# PowerMeasuringIC.net
KiCad netlist of a schematic drawn in EAGLE
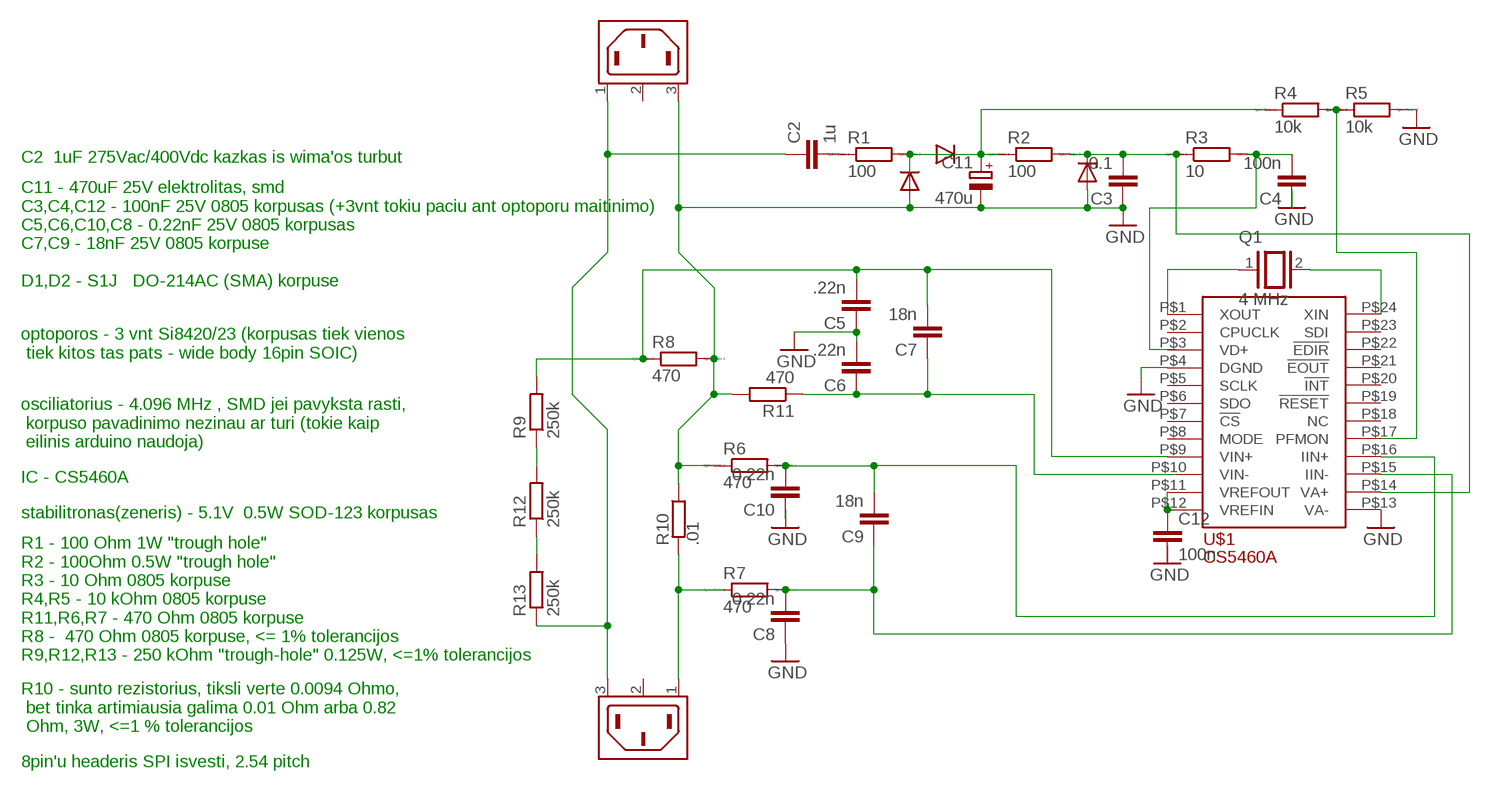
[diagram p0: schematic, sheet 1]

(export (version "E")
  (design (tool "Eeschema 10.0.6"))
  (components
    (comp (ref "C2")
      (value "1u")
      (footprint "eagle-import:C1206")
      (libsource (lib "eagle-import") (part "C-EUC1206"))
    )
    (comp (ref "C3")
      (value "0.1")
      (footprint "eagle-import:C1206")
      (libsource (lib "eagle-import") (part "C-EUC1206"))
    )
    (comp (ref "C4")
      (value "100n")
      (footprint "eagle-import:C1206")
      (libsource (lib "eagle-import") (part "C-EUC1206"))
    )
    (comp (ref "C5")
      (value ".22n")
      (footprint "eagle-import:C1206")
      (libsource (lib "eagle-import") (part "C-EUC1206"))
    )
    (comp (ref "C6")
      (value ".22n")
      (footprint "eagle-import:C1206")
      (libsource (lib "eagle-import") (part "C-EUC1206"))
    )
    (comp (ref "C7")
      (value "18n")
      (footprint "eagle-import:C1206")
      (libsource (lib "eagle-import") (part "C-EUC1206"))
    )
    (comp (ref "C8")
      (value "0.22n")
      (footprint "eagle-import:C1206")
      (libsource (lib "eagle-import") (part "C-EUC1206"))
    )
    (comp (ref "C9")
      (value "18n")
      (footprint "eagle-import:C1206")
      (libsource (lib "eagle-import") (part "C-EUC1206"))
    )
    (comp (ref "C10")
      (value "0.22n")
      (footprint "eagle-import:C1206")
      (libsource (lib "eagle-import") (part "C-EUC1206"))
    )
    (comp (ref "C11")
      (value "470u")
      (footprint "eagle-import:153CLV-0807")
      (libsource (lib "eagle-import") (part "CPOL-EU153CLV-0807"))
    )
    (comp (ref "C12")
      (value "100n")
      (footprint "eagle-import:C025-024X044")
      (libsource (lib "eagle-import") (part "C-EU025-024X044"))
    )
    (comp (ref "Q1")
      (value "4 MHz")
      (footprint "eagle-import:Q")
      (libsource (lib "eagle-import") (part "XTAL"))
    )
    (comp (ref "R1")
      (value "100")
      (footprint "eagle-import:R4527")
      (libsource (lib "eagle-import") (part "RR4527"))
    )
    (comp (ref "R2")
      (value "100")
      (footprint "eagle-import:R4527")
      (libsource (lib "eagle-import") (part "RR4527"))
    )
    (comp (ref "R3")
      (value "10")
      (footprint "eagle-import:R4527")
      (libsource (lib "eagle-import") (part "RR4527"))
    )
    (comp (ref "R4")
      (value "10k")
      (footprint "eagle-import:R4527")
      (libsource (lib "eagle-import") (part "RR4527"))
    )
    (comp (ref "R5")
      (value "10k")
      (footprint "eagle-import:R4527")
      (libsource (lib "eagle-import") (part "RR4527"))
    )
    (comp (ref "R6")
      (value "470")
      (footprint "eagle-import:R4527")
      (libsource (lib "eagle-import") (part "RR4527"))
    )
    (comp (ref "R7")
      (value "470")
      (footprint "eagle-import:R4527")
      (libsource (lib "eagle-import") (part "RR4527"))
    )
    (comp (ref "R8")
      (value "470")
      (footprint "eagle-import:R4527")
      (libsource (lib "eagle-import") (part "RR4527"))
    )
    (comp (ref "R9")
      (value "250k")
      (footprint "eagle-import:0204_5")
      (libsource (lib "eagle-import") (part "R-EU_0204/5"))
    )
    (comp (ref "R10")
      (value ".01")
      (footprint "eagle-import:SMT-WAV")
      (libsource (lib "eagle-import") (part "SMT-WAV"))
    )
    (comp (ref "R11")
      (value "470")
      (footprint "eagle-import:0207_7")
      (libsource (lib "eagle-import") (part "R-EU_0207/7"))
    )
    (comp (ref "R12")
      (value "250k")
      (footprint "eagle-import:0204_5")
      (libsource (lib "eagle-import") (part "R-EU_0204/5"))
    )
    (comp (ref "R13")
      (value "250k")
      (footprint "eagle-import:0204_5")
      (libsource (lib "eagle-import") (part "R-EU_0204/5"))
    )
    (comp (ref "U$1")
      (value "CS4560ASSOP24")
      (footprint "eagle-import:SSOP24")
      (libsource (lib "eagle-import") (part "CS4560ASSOP24"))
    )
    (comp (ref "X1")
      (value "6ESRM-P")
      (footprint "eagle-import:6ESRM-P")
      (fields (field (name "MF") "TYCO ELECTRONICS"))
      (libsource (lib "eagle-import") (part "6ESRM-P"))
    )
    (comp (ref "X2")
      (value "6ESRM-P")
      (footprint "eagle-import:6ESRM-P")
      (fields (field (name "MF") "TYCO ELECTRONICS"))
      (libsource (lib "eagle-import") (part "6ESRM-P"))
    )
  )
  (nets
    (net (code "1") (name "GND") (class "Default")
      (node (ref "C10") (pin "1") (pinfunction "1_1") (pintype "passive"))
      (node (ref "C11") (pin "-") (pinfunction "-_-") (pintype "passive"))
      (node (ref "C12") (pin "2") (pinfunction "2_2") (pintype "passive"))
      (node (ref "C3") (pin "1") (pinfunction "1_1") (pintype "passive"))
      (node (ref "C4") (pin "1") (pinfunction "1_1") (pintype "passive"))
      (node (ref "C5") (pin "1") (pinfunction "1_1") (pintype "passive"))
      (node (ref "C6") (pin "2") (pinfunction "2_2") (pintype "passive"))
      (node (ref "C8") (pin "1") (pinfunction "1_1") (pintype "passive"))
      (node (ref "R10") (pin "1") (pinfunction "1_1") (pintype "passive"))
      (node (ref "R11") (pin "2") (pinfunction "2_2") (pintype "passive"))
      (node (ref "R5") (pin "2") (pinfunction "2_2") (pintype "passive"))
      (node (ref "R6") (pin "1") (pinfunction "1_1") (pintype "passive"))
      (node (ref "R8") (pin "2") (pinfunction "2_2") (pintype "passive"))
      (node (ref "U$1") (pin "P$13") (pinfunction "VA-_P$13") (pintype "bidirectional"))
      (node (ref "U$1") (pin "P$4") (pinfunction "DGND_P$4") (pintype "bidirectional"))
      (node (ref "X1") (pin "3") (pinfunction "AC2_3") (pintype "passive"))
    )
    (net (code "2") (name "Net-(C2-Pad2)") (class "Default")
      (node (ref "C2") (pin "2") (pinfunction "2_2") (pintype "passive"))
      (node (ref "R1") (pin "1") (pinfunction "1_1") (pintype "passive"))
    )
    (net (code "3") (name "Net-(C4-Pad2)") (class "Default")
      (node (ref "C4") (pin "2") (pinfunction "2_2") (pintype "passive"))
      (node (ref "R3") (pin "2") (pinfunction "2_2") (pintype "passive"))
    )
    (net (code "4") (name "Net-(C6-Pad1)") (class "Default")
      (node (ref "C6") (pin "1") (pinfunction "1_1") (pintype "passive"))
      (node (ref "C7") (pin "1") (pinfunction "1_1") (pintype "passive"))
      (node (ref "R11") (pin "1") (pinfunction "1_1") (pintype "passive"))
    )
    (net (code "5") (name "Net-(C11-Pad+)") (class "Default")
      (node (ref "C11") (pin "+") (pinfunction "+_+") (pintype "passive"))
      (node (ref "R1") (pin "2") (pinfunction "2_2") (pintype "passive"))
      (node (ref "R2") (pin "1") (pinfunction "1_1") (pintype "passive"))
      (node (ref "R4") (pin "1") (pinfunction "1_1") (pintype "passive"))
    )
    (net (code "6") (name "Net-(R12-Pad1)") (class "Default")
      (node (ref "R12") (pin "1") (pinfunction "1_1") (pintype "passive"))
      (node (ref "R13") (pin "2") (pinfunction "2_2") (pintype "passive"))
    )
    (net (code "7") (name "Net-(R12-Pad2)") (class "Default")
      (node (ref "R12") (pin "2") (pinfunction "2_2") (pintype "passive"))
      (node (ref "R9") (pin "1") (pinfunction "1_1") (pintype "passive"))
    )
    (net (code "8") (name "Net-(U$1-IIN+)") (class "Default")
      (node (ref "C10") (pin "2") (pinfunction "2_2") (pintype "passive"))
      (node (ref "C9") (pin "2") (pinfunction "2_2") (pintype "passive"))
      (node (ref "R6") (pin "2") (pinfunction "2_2") (pintype "passive"))
      (node (ref "U$1") (pin "P$16") (pinfunction "IIN+_P$16") (pintype "bidirectional"))
    )
    (net (code "9") (name "Net-(U$1-IIN-)") (class "Default")
      (node (ref "C8") (pin "2") (pinfunction "2_2") (pintype "passive"))
      (node (ref "C9") (pin "1") (pinfunction "1_1") (pintype "passive"))
      (node (ref "R7") (pin "2") (pinfunction "2_2") (pintype "passive"))
      (node (ref "U$1") (pin "P$15") (pinfunction "IIN-_P$15") (pintype "bidirectional"))
    )
    (net (code "10") (name "Net-(U$1-PFMON)") (class "Default")
      (node (ref "R4") (pin "2") (pinfunction "2_2") (pintype "passive"))
      (node (ref "R5") (pin "1") (pinfunction "1_1") (pintype "passive"))
      (node (ref "U$1") (pin "P$17") (pinfunction "PFMON_P$17") (pintype "bidirectional"))
    )
    (net (code "11") (name "Net-(U$1-VA+)") (class "Default")
      (node (ref "C3") (pin "2") (pinfunction "2_2") (pintype "passive"))
      (node (ref "R2") (pin "2") (pinfunction "2_2") (pintype "passive"))
      (node (ref "R3") (pin "1") (pinfunction "1_1") (pintype "passive"))
      (node (ref "U$1") (pin "P$14") (pinfunction "VA+_P$14") (pintype "bidirectional"))
    )
    (net (code "12") (name "Net-(U$1-VIN+)") (class "Default")
      (node (ref "C5") (pin "2") (pinfunction "2_2") (pintype "passive"))
      (node (ref "C7") (pin "2") (pinfunction "2_2") (pintype "passive"))
      (node (ref "R8") (pin "1") (pinfunction "1_1") (pintype "passive"))
      (node (ref "R9") (pin "2") (pinfunction "2_2") (pintype "passive"))
      (node (ref "U$1") (pin "P$9") (pinfunction "VIN+_P$9") (pintype "bidirectional"))
    )
    (net (code "13") (name "Net-(U$1-VREFIN)") (class "Default")
      (node (ref "C12") (pin "1") (pinfunction "1_1") (pintype "passive"))
      (node (ref "U$1") (pin "P$11") (pinfunction "VREFOUT_P$11") (pintype "bidirectional"))
      (node (ref "U$1") (pin "P$12") (pinfunction "VREFIN_P$12") (pintype "bidirectional"))
    )
    (net (code "14") (name "Net-(U$1-XIN)") (class "Default")
      (node (ref "Q1") (pin "2") (pinfunction "2_2") (pintype "passive"))
      (node (ref "U$1") (pin "P$24") (pinfunction "XIN_P$24") (pintype "bidirectional"))
    )
    (net (code "15") (name "Net-(U$1-XOUT)") (class "Default")
      (node (ref "Q1") (pin "1") (pinfunction "1_1") (pintype "passive"))
      (node (ref "U$1") (pin "P$1") (pinfunction "XOUT_P$1") (pintype "bidirectional"))
    )
    (net (code "16") (name "Net-(X1-AC1)") (class "Default")
      (node (ref "C2") (pin "1") (pinfunction "1_1") (pintype "passive"))
      (node (ref "R13") (pin "1") (pinfunction "1_1") (pintype "passive"))
      (node (ref "X1") (pin "1") (pinfunction "AC1_1") (pintype "passive"))
      (node (ref "X2") (pin "3") (pinfunction "AC2_3") (pintype "passive"))
    )
    (net (code "17") (name "Net-(X2-AC1)") (class "Default")
      (node (ref "R10") (pin "2") (pinfunction "2_2") (pintype "passive"))
      (node (ref "X2") (pin "1") (pinfunction "AC1_1") (pintype "passive"))
    )
    (net (code "18") (name "unconnected-(R7-Pad1)") (class "Default")
      (node (ref "R7") (pin "1") (pinfunction "1_1") (pintype "passive"))
    )
    (net (code "19") (name "unconnected-(U$1-CPUCLK-PadP$2)") (class "Default")
      (node (ref "U$1") (pin "P$2") (pinfunction "CPUCLK_P$2") (pintype "bidirectional"))
    )
    (net (code "20") (name "unconnected-(U$1-MODE-PadP$8)") (class "Default")
      (node (ref "U$1") (pin "P$8") (pinfunction "MODE_P$8") (pintype "bidirectional"))
    )
    (net (code "21") (name "unconnected-(U$1-NC-PadP$18)") (class "Default")
      (node (ref "U$1") (pin "P$18") (pinfunction "NC_P$18") (pintype "bidirectional"))
    )
    (net (code "22") (name "unconnected-(U$1-SCLK-PadP$5)") (class "Default")
      (node (ref "U$1") (pin "P$5") (pinfunction "SCLK_P$5") (pintype "bidirectional"))
    )
    (net (code "23") (name "unconnected-(U$1-SDI-PadP$23)") (class "Default")
      (node (ref "U$1") (pin "P$23") (pinfunction "SDI_P$23") (pintype "bidirectional"))
    )
    (net (code "24") (name "unconnected-(U$1-SDO-PadP$6)") (class "Default")
      (node (ref "U$1") (pin "P$6") (pinfunction "SDO_P$6") (pintype "bidirectional"))
    )
    (net (code "25") (name "unconnected-(U$1-VD+-PadP$3)") (class "Default")
      (node (ref "U$1") (pin "P$3") (pinfunction "VD+_P$3") (pintype "bidirectional"))
    )
    (net (code "26") (name "unconnected-(U$1-VIN--PadP$10)") (class "Default")
      (node (ref "U$1") (pin "P$10") (pinfunction "VIN-_P$10") (pintype "bidirectional"))
    )
    (net (code "27") (name "unconnected-(U$1-~{CS}-PadP$7)") (class "Default")
      (node (ref "U$1") (pin "P$7") (pinfunction "~{CS}_P$7") (pintype "bidirectional"))
    )
    (net (code "28") (name "unconnected-(U$1-~{EDIR}-PadP$22)") (class "Default")
      (node (ref "U$1") (pin "P$22") (pinfunction "~{EDIR}_P$22") (pintype "bidirectional"))
    )
    (net (code "29") (name "unconnected-(U$1-~{EOUT}-PadP$21)") (class "Default")
      (node (ref "U$1") (pin "P$21") (pinfunction "~{EOUT}_P$21") (pintype "bidirectional"))
    )
    (net (code "30") (name "unconnected-(U$1-~{INT}-PadP$20)") (class "Default")
      (node (ref "U$1") (pin "P$20") (pinfunction "~{INT}_P$20") (pintype "bidirectional"))
    )
    (net (code "31") (name "unconnected-(U$1-~{RESET}-PadP$19)") (class "Default")
      (node (ref "U$1") (pin "P$19") (pinfunction "~{RESET}_P$19") (pintype "bidirectional"))
    )
    (net (code "32") (name "unconnected-(X1-SH-Pad2)") (class "Default")
      (node (ref "X1") (pin "2") (pinfunction "SH_2") (pintype "passive"))
    )
    (net (code "33") (name "unconnected-(X2-SH-Pad2)") (class "Default")
      (node (ref "X2") (pin "2") (pinfunction "SH_2") (pintype "passive"))
    )
  )
)
